# -1.net
KiCad netlist of a schematic drawn in Altium Designer
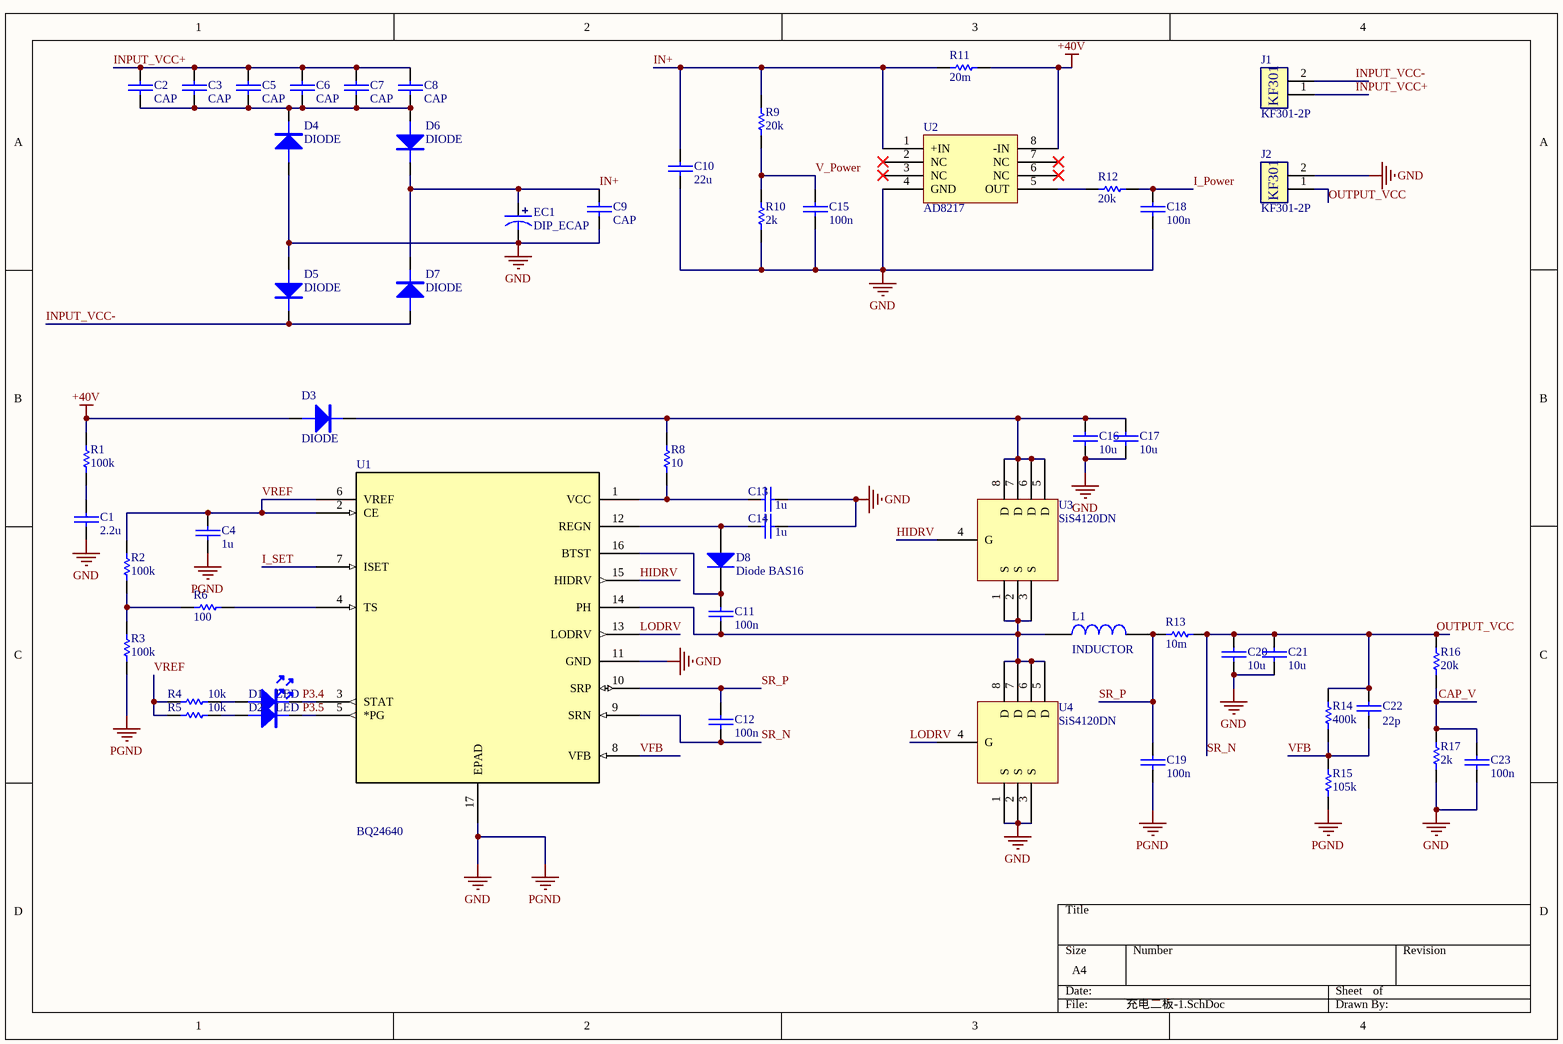
[diagram p0: 充电二板-1.SchDoc]

(export (version "E")
  (design (tool "Eeschema 10.0.6"))
  (components
    (comp (ref "C1")
      (value "2.2u")
      (footprint "0603C")
      (description "无极性电容")
      (libsource (lib "电容") (part "CAP"))
    )
    (comp (ref "C2")
      (value "CAP")
      (footprint "1206C")
      (description "无极性电容")
      (libsource (lib "电容") (part "CAP"))
    )
    (comp (ref "C3")
      (value "CAP")
      (footprint "1206C")
      (description "无极性电容")
      (libsource (lib "电容") (part "CAP"))
    )
    (comp (ref "C4")
      (value "1u")
      (footprint "0603C")
      (description "无极性电容")
      (libsource (lib "电容") (part "CAP"))
    )
    (comp (ref "C5")
      (value "CAP")
      (footprint "1206C")
      (description "无极性电容")
      (libsource (lib "电容") (part "CAP"))
    )
    (comp (ref "C6")
      (value "CAP")
      (footprint "1206C")
      (description "无极性电容")
      (libsource (lib "电容") (part "CAP"))
    )
    (comp (ref "C7")
      (value "CAP")
      (footprint "1206C")
      (description "无极性电容")
      (libsource (lib "电容") (part "CAP"))
    )
    (comp (ref "C8")
      (value "CAP")
      (footprint "1206C")
      (description "无极性电容")
      (libsource (lib "电容") (part "CAP"))
    )
    (comp (ref "C9")
      (value "CAP")
      (footprint "1206C")
      (description "无极性电容")
      (libsource (lib "电容") (part "CAP"))
    )
    (comp (ref "C10")
      (value "22u")
      (footprint "1206C")
      (description "无极性电容")
      (libsource (lib "电容") (part "CAP"))
    )
    (comp (ref "C11")
      (value "100n")
      (footprint "0603C")
      (description "无极性电容")
      (libsource (lib "电容") (part "CAP"))
    )
    (comp (ref "C12")
      (value "100n")
      (footprint "0603C")
      (description "无极性电容")
      (libsource (lib "电容") (part "CAP"))
    )
    (comp (ref "C13")
      (value "1u")
      (footprint "0603C")
      (description "无极性电容")
      (libsource (lib "电容") (part "CAP"))
    )
    (comp (ref "C14")
      (value "1u")
      (footprint "0603C")
      (description "无极性电容")
      (libsource (lib "电容") (part "CAP"))
    )
    (comp (ref "C15")
      (value "100n")
      (footprint "0603C")
      (description "无极性电容")
      (libsource (lib "电容") (part "CAP"))
    )
    (comp (ref "C16")
      (value "10u")
      (footprint "1206C")
      (description "无极性电容")
      (libsource (lib "电容") (part "CAP"))
    )
    (comp (ref "C17")
      (value "10u")
      (footprint "1206C")
      (description "无极性电容")
      (libsource (lib "电容") (part "CAP"))
    )
    (comp (ref "C18")
      (value "100n")
      (footprint "0603C")
      (description "无极性电容")
      (libsource (lib "电容") (part "CAP"))
    )
    (comp (ref "C19")
      (value "100n")
      (footprint "0603C")
      (description "无极性电容")
      (libsource (lib "电容") (part "CAP"))
    )
    (comp (ref "C20")
      (value "10u")
      (footprint "1206C")
      (description "无极性电容")
      (libsource (lib "电容") (part "CAP"))
    )
    (comp (ref "C21")
      (value "10u")
      (footprint "1206C")
      (description "无极性电容")
      (libsource (lib "电容") (part "CAP"))
    )
    (comp (ref "C22")
      (value "22p")
      (footprint "0603C")
      (description "无极性电容")
      (libsource (lib "电容") (part "CAP"))
    )
    (comp (ref "C23")
      (value "100n")
      (footprint "0603C")
      (description "无极性电容")
      (libsource (lib "电容") (part "CAP"))
    )
    (comp (ref "D1") (value "LED") (footprint "LED-0603W") (libsource (lib "LED") (part "LED")))
    (comp (ref "D2") (value "LED") (footprint "LED-0603W") (libsource (lib "LED") (part "LED")))
    (comp (ref "D3")
      (value "DIODE")
      (footprint "SMA/DO-214AC")
      (description "普通二极管")
      (libsource (lib "二极管") (part "DIODE"))
    )
    (comp (ref "D4")
      (value "DIODE")
      (footprint "SMA/DO-214AC")
      (description "普通二极管")
      (libsource (lib "二极管") (part "DIODE"))
    )
    (comp (ref "D5")
      (value "DIODE")
      (footprint "SMA/DO-214AC")
      (description "普通二极管")
      (libsource (lib "二极管") (part "DIODE"))
    )
    (comp (ref "D6")
      (value "DIODE")
      (footprint "SMA/DO-214AC")
      (description "普通二极管")
      (libsource (lib "二极管") (part "DIODE"))
    )
    (comp (ref "D7")
      (value "DIODE")
      (footprint "SMA/DO-214AC")
      (description "普通二极管")
      (libsource (lib "二极管") (part "DIODE"))
    )
    (comp (ref "D8")
      (value "Diode BAS16")
      (footprint "SOT-23_N")
      (description "Silicon Switching Diode for High-Speed Switching")
      (fields (field (name "PUBLISHER") "Altium Limited"))
      (libsource (lib "Miscellaneous Devices") (part "Diode BAS16"))
    )
    (comp (ref "EC1")
      (value "DIP_ECAP")
      (footprint "DIP-EC3.5X8X11.5")
      (description "直插电解电容")
      (libsource (lib "电容") (part "DIP_ECAP"))
    )
    (comp (ref "J1")
      (value "KF301-2P")
      (footprint "KF301-5.0-2P")
      (libsource (lib "KF301") (part "KF301-2P"))
    )
    (comp (ref "J2")
      (value "KF301-2P")
      (footprint "KF301-5.0-2P")
      (libsource (lib "KF301") (part "KF301-2P"))
    )
    (comp (ref "L1") (value "INDUCTOR") (footprint "CDRH73") (libsource (lib "电感") (part "INDUCTOR")))
    (comp (ref "R1") (value "100k") (footprint "0603R") (libsource (lib "电阻") (part "RES")))
    (comp (ref "R2") (value "100k") (footprint "0603R") (libsource (lib "电阻") (part "RES")))
    (comp (ref "R3") (value "100k") (footprint "0603R") (libsource (lib "电阻") (part "RES")))
    (comp (ref "R4") (value "10k") (footprint "0603R") (libsource (lib "电阻") (part "RES")))
    (comp (ref "R5") (value "10k") (footprint "0603R") (libsource (lib "电阻") (part "RES")))
    (comp (ref "R6") (value "100") (footprint "0603R") (libsource (lib "电阻") (part "RES")))
    (comp (ref "R8") (value "10") (footprint "0603R") (libsource (lib "电阻") (part "RES")))
    (comp (ref "R9") (value "20k") (footprint "0603R") (libsource (lib "电阻") (part "RES")))
    (comp (ref "R10") (value "2k") (footprint "0603R") (libsource (lib "电阻") (part "RES")))
    (comp (ref "R11") (value "20m") (footprint "2512R") (libsource (lib "电阻") (part "RES")))
    (comp (ref "R12") (value "20k") (footprint "0603R") (libsource (lib "电阻") (part "RES")))
    (comp (ref "R13") (value "10m") (footprint "2512R") (libsource (lib "电阻") (part "RES")))
    (comp (ref "R14") (value "400k") (footprint "0603R") (libsource (lib "电阻") (part "RES")))
    (comp (ref "R15") (value "105k") (footprint "0603R") (libsource (lib "电阻") (part "RES")))
    (comp (ref "R16") (value "20k") (footprint "0603R") (libsource (lib "电阻") (part "RES")))
    (comp (ref "R17") (value "2k") (footprint "0603R") (libsource (lib "电阻") (part "RES")))
    (comp (ref "U1") (value "BQ24640") (footprint "BQ24640") (libsource (lib "charge") (part "BQ24640")))
    (comp (ref "U2") (value "AD8217") (footprint "AD8127") (libsource (lib "charge") (part "AD8217")))
    (comp (ref "U3") (value "SiS4120DN") (footprint "SiS412DN") (libsource (lib "charge") (part "SiS4120DN")))
    (comp (ref "U4") (value "SiS4120DN") (footprint "SiS412DN") (libsource (lib "charge") (part "SiS4120DN")))
  )
  (nets
    (net (code "1") (name "+40V") (class "Default")
      (node (ref "D3") (pin "A") (pinfunction "A_A") (pintype "passive"))
      (node (ref "R1") (pin "2") (pinfunction "2_2") (pintype "passive"))
      (node (ref "R11") (pin "1") (pinfunction "1_1") (pintype "passive"))
      (node (ref "U2") (pin "8") (pinfunction "-IN_8") (pintype "passive"))
    )
    (net (code "2") (name "/CAP_V") (class "Default")
      (node (ref "C23") (pin "2") (pinfunction "2_2") (pintype "passive"))
      (node (ref "R16") (pin "1") (pinfunction "1_1") (pintype "passive"))
      (node (ref "R17") (pin "2") (pinfunction "2_2") (pintype "passive"))
    )
    (net (code "3") (name "/HIDRV") (class "Default")
      (node (ref "U1") (pin "15") (pinfunction "HIDRV_15") (pintype "output"))
      (node (ref "U3") (pin "4") (pinfunction "G_4") (pintype "passive"))
    )
    (net (code "4") (name "/IN+") (class "Default")
      (node (ref "C10") (pin "2") (pinfunction "2_2") (pintype "passive"))
      (node (ref "C9") (pin "2") (pinfunction "2_2") (pintype "passive"))
      (node (ref "D6") (pin "K") (pinfunction "K_K") (pintype "passive"))
      (node (ref "D7") (pin "K") (pinfunction "K_K") (pintype "passive"))
      (node (ref "EC1") (pin "1") (pinfunction "1_1") (pintype "passive"))
      (node (ref "R11") (pin "2") (pinfunction "2_2") (pintype "passive"))
      (node (ref "R9") (pin "2") (pinfunction "2_2") (pintype "passive"))
      (node (ref "U2") (pin "1") (pinfunction "+IN_1") (pintype "passive"))
    )
    (net (code "5") (name "/INPUT_VCC+") (class "Default")
      (node (ref "C2") (pin "2") (pinfunction "2_2") (pintype "passive"))
      (node (ref "C3") (pin "2") (pinfunction "2_2") (pintype "passive"))
      (node (ref "C5") (pin "2") (pinfunction "2_2") (pintype "passive"))
      (node (ref "C6") (pin "2") (pinfunction "2_2") (pintype "passive"))
      (node (ref "C7") (pin "2") (pinfunction "2_2") (pintype "passive"))
      (node (ref "C8") (pin "2") (pinfunction "2_2") (pintype "passive"))
      (node (ref "J1") (pin "1") (pinfunction "1_1") (pintype "passive"))
    )
    (net (code "6") (name "/INPUT_VCC-") (class "Default")
      (node (ref "D5") (pin "K") (pinfunction "K_K") (pintype "passive"))
      (node (ref "D7") (pin "A") (pinfunction "A_A") (pintype "passive"))
      (node (ref "J1") (pin "2") (pinfunction "2_2") (pintype "passive"))
    )
    (net (code "7") (name "/I_Power") (class "Default")
      (node (ref "C18") (pin "2") (pinfunction "2_2") (pintype "passive"))
      (node (ref "R12") (pin "1") (pinfunction "1_1") (pintype "passive"))
    )
    (net (code "8") (name "/I_SET") (class "Default")
      (node (ref "U1") (pin "7") (pinfunction "ISET_7") (pintype "input"))
    )
    (net (code "9") (name "/LODRV") (class "Default")
      (node (ref "U1") (pin "13") (pinfunction "LODRV_13") (pintype "output"))
      (node (ref "U4") (pin "4") (pinfunction "G_4") (pintype "passive"))
    )
    (net (code "10") (name "/OUTPUT_VCC") (class "Default")
      (node (ref "C12") (pin "2") (pinfunction "2_2") (pintype "passive"))
      (node (ref "C20") (pin "2") (pinfunction "2_2") (pintype "passive"))
      (node (ref "C21") (pin "2") (pinfunction "2_2") (pintype "passive"))
      (node (ref "C22") (pin "2") (pinfunction "2_2") (pintype "passive"))
      (node (ref "J2") (pin "1") (pinfunction "1_1") (pintype "passive"))
      (node (ref "R13") (pin "1") (pinfunction "1_1") (pintype "passive"))
      (node (ref "R14") (pin "2") (pinfunction "2_2") (pintype "passive"))
      (node (ref "R16") (pin "2") (pinfunction "2_2") (pintype "passive"))
      (node (ref "U1") (pin "9") (pinfunction "SRN_9") (pintype "input"))
    )
    (net (code "11") (name "/P3.4") (class "Default")
      (node (ref "D1") (pin "K") (pinfunction "K_K") (pintype "passive"))
      (node (ref "U1") (pin "3") (pinfunction "STAT_3") (pintype "output"))
    )
    (net (code "12") (name "/P3.5") (class "Default")
      (node (ref "D2") (pin "K") (pinfunction "K_K") (pintype "passive"))
      (node (ref "U1") (pin "5") (pinfunction "*PG_5") (pintype "output"))
    )
    (net (code "13") (name "/SR_P") (class "Default")
      (node (ref "C12") (pin "1") (pinfunction "1_1") (pintype "passive"))
      (node (ref "C19") (pin "2") (pinfunction "2_2") (pintype "passive"))
      (node (ref "L1") (pin "2") (pinfunction "2_2") (pintype "passive"))
      (node (ref "R13") (pin "2") (pinfunction "2_2") (pintype "passive"))
      (node (ref "U1") (pin "10") (pinfunction "SRP_10") (pintype "bidirectional"))
    )
    (net (code "14") (name "/VFB") (class "Default")
      (node (ref "C22") (pin "1") (pinfunction "1_1") (pintype "passive"))
      (node (ref "R14") (pin "1") (pinfunction "1_1") (pintype "passive"))
      (node (ref "R15") (pin "2") (pinfunction "2_2") (pintype "passive"))
      (node (ref "U1") (pin "8") (pinfunction "VFB_8") (pintype "input"))
    )
    (net (code "15") (name "/VREF") (class "Default")
      (node (ref "C4") (pin "2") (pinfunction "2_2") (pintype "passive"))
      (node (ref "R2") (pin "2") (pinfunction "2_2") (pintype "passive"))
      (node (ref "R4") (pin "2") (pinfunction "2_2") (pintype "passive"))
      (node (ref "R5") (pin "2") (pinfunction "2_2") (pintype "passive"))
      (node (ref "U1") (pin "2") (pinfunction "CE_2") (pintype "input"))
      (node (ref "U1") (pin "6") (pinfunction "VREF_6") (pintype "power_in"))
    )
    (net (code "16") (name "/V_Power") (class "Default")
      (node (ref "C15") (pin "2") (pinfunction "2_2") (pintype "passive"))
      (node (ref "R10") (pin "2") (pinfunction "2_2") (pintype "passive"))
      (node (ref "R9") (pin "1") (pinfunction "1_1") (pintype "passive"))
    )
    (net (code "17") (name "GND") (class "Default")
      (node (ref "C1") (pin "1") (pinfunction "1_1") (pintype "passive"))
      (node (ref "C10") (pin "1") (pinfunction "1_1") (pintype "passive"))
      (node (ref "C13") (pin "1") (pinfunction "1_1") (pintype "passive"))
      (node (ref "C14") (pin "1") (pinfunction "1_1") (pintype "passive"))
      (node (ref "C15") (pin "1") (pinfunction "1_1") (pintype "passive"))
      (node (ref "C16") (pin "1") (pinfunction "1_1") (pintype "passive"))
      (node (ref "C17") (pin "1") (pinfunction "1_1") (pintype "passive"))
      (node (ref "C18") (pin "1") (pinfunction "1_1") (pintype "passive"))
      (node (ref "C19") (pin "1") (pinfunction "1_1") (pintype "passive"))
      (node (ref "C20") (pin "1") (pinfunction "1_1") (pintype "passive"))
      (node (ref "C21") (pin "1") (pinfunction "1_1") (pintype "passive"))
      (node (ref "C23") (pin "1") (pinfunction "1_1") (pintype "passive"))
      (node (ref "C4") (pin "1") (pinfunction "1_1") (pintype "passive"))
      (node (ref "C9") (pin "1") (pinfunction "1_1") (pintype "passive"))
      (node (ref "D4") (pin "A") (pinfunction "A_A") (pintype "passive"))
      (node (ref "D5") (pin "A") (pinfunction "A_A") (pintype "passive"))
      (node (ref "EC1") (pin "2") (pinfunction "2_2") (pintype "passive"))
      (node (ref "J2") (pin "2") (pinfunction "2_2") (pintype "passive"))
      (node (ref "R10") (pin "1") (pinfunction "1_1") (pintype "passive"))
      (node (ref "R15") (pin "1") (pinfunction "1_1") (pintype "passive"))
      (node (ref "R17") (pin "1") (pinfunction "1_1") (pintype "passive"))
      (node (ref "R3") (pin "1") (pinfunction "1_1") (pintype "passive"))
      (node (ref "U1") (pin "11") (pinfunction "GND_11") (pintype "power_in"))
      (node (ref "U1") (pin "17") (pinfunction "EPAD_17") (pintype "power_in"))
      (node (ref "U2") (pin "4") (pinfunction "GND_4") (pintype "passive"))
      (node (ref "U4") (pin "1") (pinfunction "S_1") (pintype "passive"))
      (node (ref "U4") (pin "2") (pinfunction "S_2") (pintype "passive"))
      (node (ref "U4") (pin "3") (pinfunction "S_3") (pintype "passive"))
    )
    (net (code "18") (name "Net-(C1-Pad2)") (class "Default")
      (node (ref "C1") (pin "2") (pinfunction "2_2") (pintype "passive"))
      (node (ref "R1") (pin "1") (pinfunction "1_1") (pintype "passive"))
    )
    (net (code "19") (name "Net-(C2-Pad1)") (class "Default")
      (node (ref "C2") (pin "1") (pinfunction "1_1") (pintype "passive"))
      (node (ref "C3") (pin "1") (pinfunction "1_1") (pintype "passive"))
      (node (ref "C5") (pin "1") (pinfunction "1_1") (pintype "passive"))
      (node (ref "C6") (pin "1") (pinfunction "1_1") (pintype "passive"))
      (node (ref "C7") (pin "1") (pinfunction "1_1") (pintype "passive"))
      (node (ref "C8") (pin "1") (pinfunction "1_1") (pintype "passive"))
      (node (ref "D4") (pin "K") (pinfunction "K_K") (pintype "passive"))
      (node (ref "D6") (pin "A") (pinfunction "A_A") (pintype "passive"))
    )
    (net (code "20") (name "Net-(C16-Pad2)") (class "Default")
      (node (ref "C16") (pin "2") (pinfunction "2_2") (pintype "passive"))
      (node (ref "C17") (pin "2") (pinfunction "2_2") (pintype "passive"))
      (node (ref "D3") (pin "K") (pinfunction "K_K") (pintype "passive"))
      (node (ref "R8") (pin "1") (pinfunction "1_1") (pintype "passive"))
      (node (ref "U3") (pin "5") (pinfunction "D_5") (pintype "passive"))
      (node (ref "U3") (pin "6") (pinfunction "D_6") (pintype "passive"))
      (node (ref "U3") (pin "7") (pinfunction "D_7") (pintype "passive"))
      (node (ref "U3") (pin "8") (pinfunction "D_8") (pintype "passive"))
    )
    (net (code "21") (name "Net-(D1-PadA)") (class "Default")
      (node (ref "D1") (pin "A") (pinfunction "A_A") (pintype "passive"))
      (node (ref "R4") (pin "1") (pinfunction "1_1") (pintype "passive"))
    )
    (net (code "22") (name "Net-(D2-PadA)") (class "Default")
      (node (ref "D2") (pin "A") (pinfunction "A_A") (pintype "passive"))
      (node (ref "R5") (pin "1") (pinfunction "1_1") (pintype "passive"))
    )
    (net (code "23") (name "Net-(D8-A)") (class "Default")
      (node (ref "C14") (pin "2") (pinfunction "2_2") (pintype "passive"))
      (node (ref "D8") (pin "1") (pinfunction "A_1") (pintype "passive"))
      (node (ref "U1") (pin "12") (pinfunction "REGN_12") (pintype "power_in"))
    )
    (net (code "24") (name "Net-(D8-K)") (class "Default")
      (node (ref "C11") (pin "1") (pinfunction "1_1") (pintype "passive"))
      (node (ref "D8") (pin "3") (pinfunction "K_3") (pintype "passive"))
      (node (ref "U1") (pin "16") (pinfunction "BTST_16") (pintype "power_in"))
    )
    (net (code "25") (name "Net-(R2-Pad1)") (class "Default")
      (node (ref "R2") (pin "1") (pinfunction "1_1") (pintype "passive"))
      (node (ref "R3") (pin "2") (pinfunction "2_2") (pintype "passive"))
      (node (ref "R6") (pin "2") (pinfunction "2_2") (pintype "passive"))
    )
    (net (code "26") (name "Net-(U1-PH)") (class "Default")
      (node (ref "C11") (pin "2") (pinfunction "2_2") (pintype "passive"))
      (node (ref "L1") (pin "1") (pinfunction "1_1") (pintype "passive"))
      (node (ref "U1") (pin "14") (pinfunction "PH_14") (pintype "power_in"))
      (node (ref "U3") (pin "1") (pinfunction "S_1") (pintype "passive"))
      (node (ref "U3") (pin "2") (pinfunction "S_2") (pintype "passive"))
      (node (ref "U3") (pin "3") (pinfunction "S_3") (pintype "passive"))
      (node (ref "U4") (pin "5") (pinfunction "D_5") (pintype "passive"))
      (node (ref "U4") (pin "6") (pinfunction "D_6") (pintype "passive"))
      (node (ref "U4") (pin "7") (pinfunction "D_7") (pintype "passive"))
      (node (ref "U4") (pin "8") (pinfunction "D_8") (pintype "passive"))
    )
    (net (code "27") (name "Net-(U1-TS)") (class "Default")
      (node (ref "R6") (pin "1") (pinfunction "1_1") (pintype "passive"))
      (node (ref "U1") (pin "4") (pinfunction "TS_4") (pintype "input"))
    )
    (net (code "28") (name "Net-(U1-VCC)") (class "Default")
      (node (ref "C13") (pin "2") (pinfunction "2_2") (pintype "passive"))
      (node (ref "R8") (pin "2") (pinfunction "2_2") (pintype "passive"))
      (node (ref "U1") (pin "1") (pinfunction "VCC_1") (pintype "power_in"))
    )
    (net (code "29") (name "Net-(U2-OUT)") (class "Default")
      (node (ref "R12") (pin "2") (pinfunction "2_2") (pintype "passive"))
      (node (ref "U2") (pin "5") (pinfunction "OUT_5") (pintype "passive"))
    )
    (net (code "30") (name "unconnected-(U2-NC-Pad2)") (class "Default")
      (node (ref "U2") (pin "2") (pinfunction "NC_2") (pintype "passive+no_connect"))
    )
    (net (code "31") (name "unconnected-(U2-NC-Pad3)") (class "Default")
      (node (ref "U2") (pin "3") (pinfunction "NC_3") (pintype "passive+no_connect"))
    )
    (net (code "32") (name "unconnected-(U2-NC-Pad6)") (class "Default")
      (node (ref "U2") (pin "6") (pinfunction "NC_6") (pintype "passive+no_connect"))
    )
    (net (code "33") (name "unconnected-(U2-NC-Pad7)") (class "Default")
      (node (ref "U2") (pin "7") (pinfunction "NC_7") (pintype "passive+no_connect"))
    )
  )
)
